# motordriver.net
KiCad netlist of a schematic drawn in EAGLE
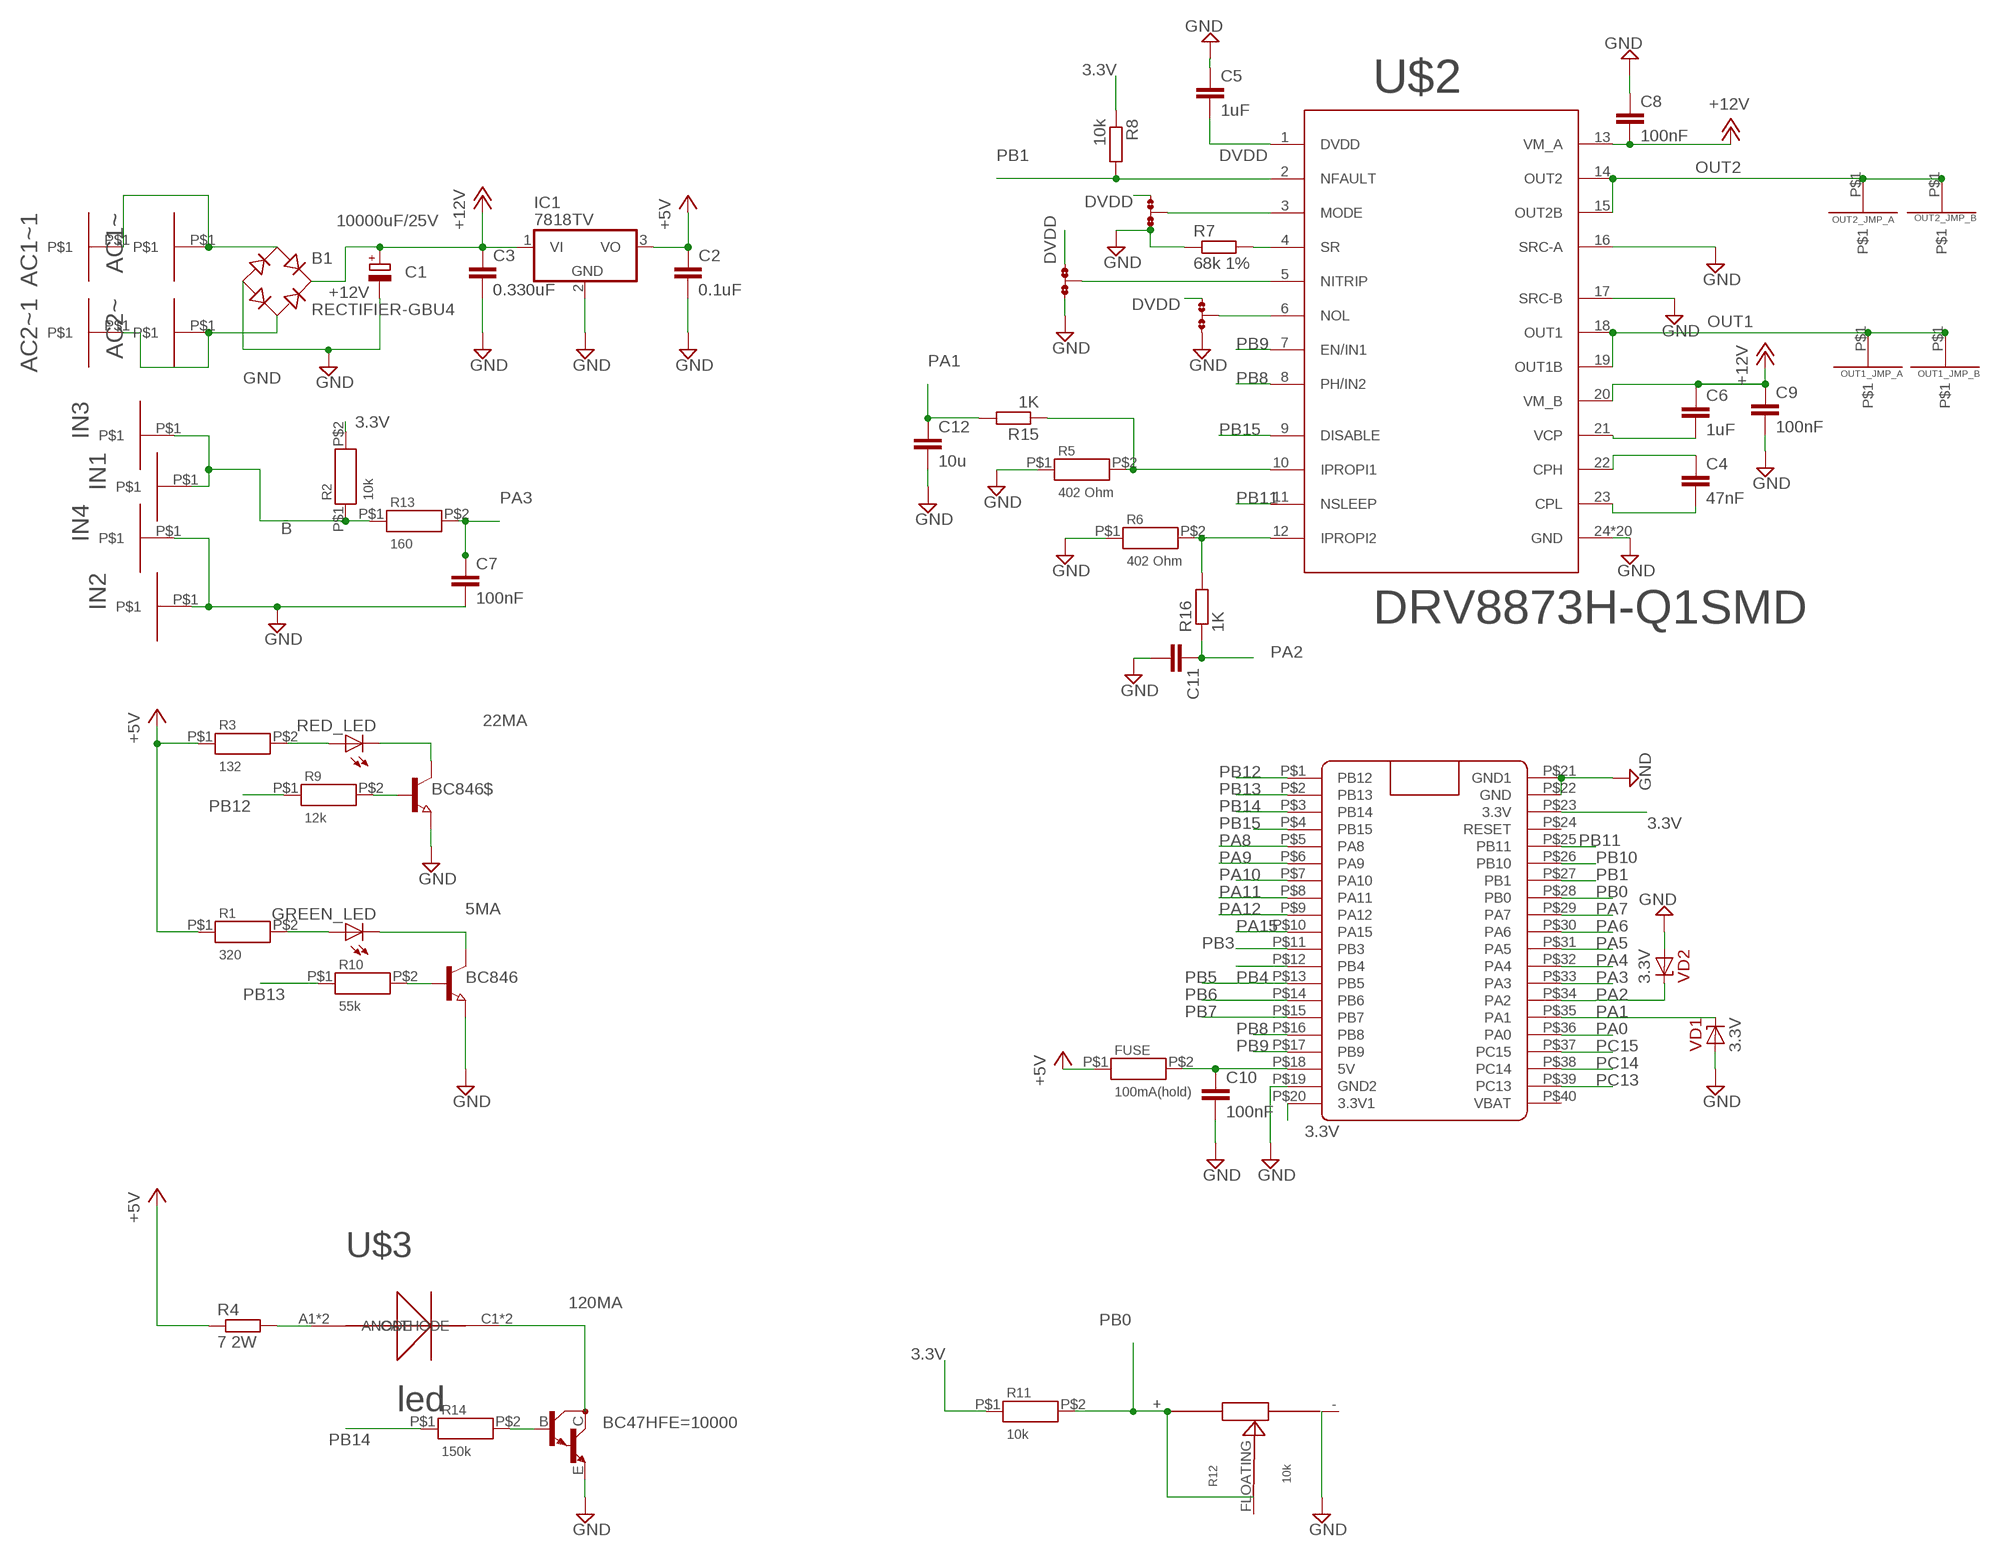
[diagram p0: schematic, sheet 1]

(export (version "E")
  (design (tool "Eeschema 10.0.6"))
  (components
    (comp (ref "AC1~")
      (value "SMDPAD")
      (footprint "eagle-import:1.5X7MMPAD")
      (libsource (lib "eagle-import") (part "SMDPAD"))
    )
    (comp (ref "AC1~1")
      (value "SMDPAD")
      (footprint "eagle-import:1.5X7MMPAD")
      (libsource (lib "eagle-import") (part "SMDPAD"))
    )
    (comp (ref "AC2~")
      (value "SMDPAD")
      (footprint "eagle-import:1.5X7MMPAD")
      (libsource (lib "eagle-import") (part "SMDPAD"))
    )
    (comp (ref "AC2~1")
      (value "SMDPAD")
      (footprint "eagle-import:1.5X7MMPAD")
      (libsource (lib "eagle-import") (part "SMDPAD"))
    )
    (comp (ref "B1")
      (value "RECTIFIER-GBU4")
      (footprint "eagle-import:GBU4")
      (libsource (lib "eagle-import") (part "RECTIFIER-GBU4"))
    )
    (comp (ref "BC47HFE=10000")
      (value "MMBTA14LT1")
      (footprint "eagle-import:SOT23-BEC")
      (libsource (lib "eagle-import") (part "MMBTA14LT1"))
    )
    (comp (ref "BC846")
      (value "NPN-TRANSISTOR_SOT23")
      (footprint "eagle-import:SOT23")
      (libsource (lib "eagle-import") (part "NPN-TRANSISTOR_SOT23"))
    )
    (comp (ref "BC846$")
      (value "NPN-TRANSISTOR_SOT23")
      (footprint "eagle-import:SOT23")
      (libsource (lib "eagle-import") (part "NPN-TRANSISTOR_SOT23"))
    )
    (comp (ref "C1")
      (value "10000uF/25V")
      (footprint "eagle-import:E7,5-18")
      (libsource (lib "eagle-import") (part "CPOL-EUE7.5-18"))
    )
    (comp (ref "C2")
      (value "0.1uF")
      (footprint "eagle-import:C1206")
      (libsource (lib "eagle-import") (part "C-EUC1206"))
    )
    (comp (ref "C3")
      (value "0.330uF")
      (footprint "eagle-import:C1206")
      (libsource (lib "eagle-import") (part "C-EUC1206"))
    )
    (comp (ref "C4")
      (value "47nF")
      (footprint "eagle-import:C1206K")
      (libsource (lib "eagle-import") (part "C-EUC1206K"))
    )
    (comp (ref "C5")
      (value "1uF")
      (footprint "eagle-import:C1206K")
      (libsource (lib "eagle-import") (part "C-EUC1206K"))
    )
    (comp (ref "C6")
      (value "1uF")
      (footprint "eagle-import:C1206K")
      (libsource (lib "eagle-import") (part "C-EUC1206K"))
    )
    (comp (ref "C7")
      (value "100nF")
      (footprint "eagle-import:C1206")
      (libsource (lib "eagle-import") (part "C-EUC1206"))
    )
    (comp (ref "C8")
      (value "100nF")
      (footprint "eagle-import:C0805")
      (libsource (lib "eagle-import") (part "C-EUC0805"))
    )
    (comp (ref "C9")
      (value "100nF")
      (footprint "eagle-import:C0805")
      (libsource (lib "eagle-import") (part "C-EUC0805"))
    )
    (comp (ref "C10")
      (value "100nF")
      (footprint "eagle-import:C0805K")
      (libsource (lib "eagle-import") (part "C-EUC0805K"))
    )
    (comp (ref "C11")
      (value "C-EUC0805K")
      (footprint "eagle-import:C0805K")
      (libsource (lib "eagle-import") (part "C-EUC0805K"))
    )
    (comp (ref "C12")
      (value "10u")
      (footprint "eagle-import:C0805K")
      (libsource (lib "eagle-import") (part "C-EUC0805K"))
    )
    (comp (ref "FUSE")
      (value "100mA(hold)")
      (footprint "eagle-import:0805")
      (libsource (lib "eagle-import") (part "RESISTOR0805_SMD"))
    )
    (comp (ref "GREEN_LED")
      (value "LEDCHIPLED_0805")
      (footprint "eagle-import:CHIPLED_0805")
      (libsource (lib "eagle-import") (part "LEDCHIPLED_0805"))
    )
    (comp (ref "IC1")
      (value "7818TV")
      (footprint "eagle-import:TO220V")
      (libsource (lib "eagle-import") (part "78TV18"))
    )
    (comp (ref "IN1")
      (value "SMDPAD")
      (footprint "eagle-import:1.5X7MMPAD")
      (libsource (lib "eagle-import") (part "SMDPAD"))
    )
    (comp (ref "IN2")
      (value "SMDPAD")
      (footprint "eagle-import:1.5X7MMPAD")
      (libsource (lib "eagle-import") (part "SMDPAD"))
    )
    (comp (ref "IN3")
      (value "SMDPAD")
      (footprint "eagle-import:1.5X7MMPAD")
      (libsource (lib "eagle-import") (part "SMDPAD"))
    )
    (comp (ref "IN4")
      (value "SMDPAD")
      (footprint "eagle-import:1.5X7MMPAD")
      (libsource (lib "eagle-import") (part "SMDPAD"))
    )
    (comp (ref "JMP1")
      (value "0R-JUMPA")
      (footprint "eagle-import:A0R-JMP")
      (libsource (lib "eagle-import") (part "0R-JUMPA"))
    )
    (comp (ref "JMP2")
      (value "0R-JUMPA")
      (footprint "eagle-import:A0R-JMP")
      (libsource (lib "eagle-import") (part "0R-JUMPA"))
    )
    (comp (ref "JMP3")
      (value "0R-JUMPA")
      (footprint "eagle-import:A0R-JMP")
      (libsource (lib "eagle-import") (part "0R-JUMPA"))
    )
    (comp (ref "OUT1_JMP_A")
      (value "SMDPAD")
      (footprint "eagle-import:1.5X7MMPAD")
      (libsource (lib "eagle-import") (part "SMDPAD"))
    )
    (comp (ref "OUT1_JMP_B")
      (value "SMDPAD")
      (footprint "eagle-import:1.5X7MMPAD")
      (libsource (lib "eagle-import") (part "SMDPAD"))
    )
    (comp (ref "OUT2_JMP_A")
      (value "SMDPAD")
      (footprint "eagle-import:1.5X7MMPAD")
      (libsource (lib "eagle-import") (part "SMDPAD"))
    )
    (comp (ref "OUT2_JMP_B")
      (value "SMDPAD")
      (footprint "eagle-import:1.5X7MMPAD")
      (libsource (lib "eagle-import") (part "SMDPAD"))
    )
    (comp (ref "R1")
      (value "320")
      (footprint "eagle-import:0805")
      (libsource (lib "eagle-import") (part "RESISTOR0805_SMD"))
    )
    (comp (ref "R2")
      (value "10k")
      (footprint "eagle-import:0805")
      (libsource (lib "eagle-import") (part "RESISTOR0805_SMD"))
    )
    (comp (ref "R3")
      (value "132")
      (footprint "eagle-import:0805")
      (libsource (lib "eagle-import") (part "RESISTOR0805_SMD"))
    )
    (comp (ref "R4")
      (value "7 2W")
      (footprint "eagle-import:R1210")
      (libsource (lib "eagle-import") (part "R-EU_R1210"))
    )
    (comp (ref "R5")
      (value "402 Ohm")
      (footprint "eagle-import:0805")
      (libsource (lib "eagle-import") (part "RESISTOR0805_SMD"))
    )
    (comp (ref "R6")
      (value "402 Ohm")
      (footprint "eagle-import:0805")
      (libsource (lib "eagle-import") (part "RESISTOR0805_SMD"))
    )
    (comp (ref "R7")
      (value "68k 1%")
      (footprint "eagle-import:R0805")
      (libsource (lib "eagle-import") (part "R-EU_R0805"))
    )
    (comp (ref "R8")
      (value "10k")
      (footprint "eagle-import:R0805")
      (libsource (lib "eagle-import") (part "R-EU_R0805"))
    )
    (comp (ref "R9")
      (value "12k")
      (footprint "eagle-import:0805")
      (libsource (lib "eagle-import") (part "RESISTOR0805_SMD"))
    )
    (comp (ref "R10")
      (value "55k")
      (footprint "eagle-import:0805")
      (libsource (lib "eagle-import") (part "RESISTOR0805_SMD"))
    )
    (comp (ref "R11")
      (value "10k")
      (footprint "eagle-import:0805")
      (libsource (lib "eagle-import") (part "RESISTOR0805_SMD"))
    )
    (comp (ref "R12")
      (value "10k")
      (footprint "eagle-import:3X1MM")
      (libsource (lib "eagle-import") (part "POTENTIOMETER"))
    )
    (comp (ref "R13")
      (value "160")
      (footprint "eagle-import:0805")
      (libsource (lib "eagle-import") (part "RESISTOR0805_SMD"))
    )
    (comp (ref "R14")
      (value "150k")
      (footprint "eagle-import:0805")
      (libsource (lib "eagle-import") (part "RESISTOR0805_SMD"))
    )
    (comp (ref "R15")
      (value "1K")
      (footprint "eagle-import:R0805")
      (libsource (lib "eagle-import") (part "R-EU_R0805"))
    )
    (comp (ref "R16")
      (value "1K")
      (footprint "eagle-import:R0805")
      (libsource (lib "eagle-import") (part "R-EU_R0805"))
    )
    (comp (ref "RED_LED")
      (value "LEDCHIPLED_0805")
      (footprint "eagle-import:CHIPLED_0805")
      (libsource (lib "eagle-import") (part "LEDCHIPLED_0805"))
    )
    (comp (ref "U$1")
      (value "BLUE_PILL")
      (footprint "eagle-import:BLUE_PILL")
      (libsource (lib "eagle-import") (part "BLUE_PILL"))
    )
    (comp (ref "U$2")
      (value "DRV8873H-Q1SMD")
      (footprint "eagle-import:HTSSOP24")
      (libsource (lib "eagle-import") (part "DRV8873H-Q1SMD"))
    )
    (comp (ref "U$3")
      (value "POWER_LED")
      (footprint "eagle-import:OSRAMLED")
      (libsource (lib "eagle-import") (part "POWER_LED"))
    )
    (comp (ref "VD1")
      (value "3.3V")
      (footprint "eagle-import:DO35-7")
      (libsource (lib "eagle-import") (part "?5.6V(1N5232)"))
    )
    (comp (ref "VD2")
      (value "3.3V")
      (footprint "eagle-import:DO35-7")
      (libsource (lib "eagle-import") (part "?5.6V(1N5232)"))
    )
  )
  (nets
    (net (code "1") (name "+5V") (class "Default")
      (node (ref "C2") (pin "1") (pinfunction "1_1") (pintype "passive"))
      (node (ref "FUSE") (pin "P$1") (pinfunction "P$1_P$1") (pintype "bidirectional"))
      (node (ref "IC1") (pin "3") (pinfunction "VO_3") (pintype "passive"))
      (node (ref "R1") (pin "P$1") (pinfunction "P$1_P$1") (pintype "bidirectional"))
      (node (ref "R3") (pin "P$1") (pinfunction "P$1_P$1") (pintype "bidirectional"))
      (node (ref "R4") (pin "1") (pinfunction "1_1") (pintype "passive"))
    )
    (net (code "2") (name "+12V") (class "Default")
      (node (ref "B1") (pin "+") (pinfunction "+_+") (pintype "passive"))
      (node (ref "C1") (pin "+") (pinfunction "+_+") (pintype "passive"))
      (node (ref "C3") (pin "1") (pinfunction "1_1") (pintype "passive"))
      (node (ref "C6") (pin "1") (pinfunction "1_1") (pintype "passive"))
      (node (ref "C8") (pin "2") (pinfunction "2_2") (pintype "passive"))
      (node (ref "C9") (pin "1") (pinfunction "1_1") (pintype "passive"))
      (node (ref "IC1") (pin "1") (pinfunction "VI_1") (pintype "input"))
      (node (ref "U$2") (pin "13") (pinfunction "VM_A_13") (pintype "power_in"))
      (node (ref "U$2") (pin "20") (pinfunction "VM_B_20") (pintype "power_in"))
    )
    (net (code "3") (name "/3.3V") (class "Default")
      (node (ref "R11") (pin "P$1") (pinfunction "P$1_P$1") (pintype "bidirectional"))
      (node (ref "R2") (pin "P$2") (pinfunction "P$2_P$2") (pintype "bidirectional"))
      (node (ref "R8") (pin "1") (pinfunction "1_1") (pintype "passive"))
      (node (ref "U$1") (pin "P$20") (pinfunction "3.3V1_P$20") (pintype "bidirectional"))
      (node (ref "U$1") (pin "P$23") (pinfunction "3.3V_P$23") (pintype "bidirectional"))
    )
    (net (code "4") (name "/5MA") (class "Default")
      (node (ref "BC846") (pin "3") (pinfunction "C_3") (pintype "passive"))
      (node (ref "GREEN_LED") (pin "C") (pinfunction "C_C") (pintype "passive"))
    )
    (net (code "5") (name "/22MA") (class "Default")
      (node (ref "BC846$") (pin "3") (pinfunction "C_3") (pintype "passive"))
      (node (ref "RED_LED") (pin "C") (pinfunction "C_C") (pintype "passive"))
    )
    (net (code "6") (name "/120MA") (class "Default")
      (node (ref "BC47HFE=10000") (pin "C") (pinfunction "C_C") (pintype "passive"))
      (node (ref "U$3") (pin "C1") (pinfunction "CATHODE_C1") (pintype "bidirectional"))
      (node (ref "U$3") (pin "C2") (pinfunction "CATHODE_C2") (pintype "bidirectional"))
    )
    (net (code "7") (name "/B") (class "Default")
      (node (ref "IN1") (pin "P$1") (pinfunction "P$1_P$1") (pintype "bidirectional"))
      (node (ref "IN3") (pin "P$1") (pinfunction "P$1_P$1") (pintype "bidirectional"))
      (node (ref "R13") (pin "P$1") (pinfunction "P$1_P$1") (pintype "bidirectional"))
      (node (ref "R2") (pin "P$1") (pinfunction "P$1_P$1") (pintype "bidirectional"))
    )
    (net (code "8") (name "/DVDD") (class "Default")
      (node (ref "C5") (pin "2") (pinfunction "2_2") (pintype "passive"))
      (node (ref "JMP1") (pin "1") (pinfunction "1_1") (pintype "passive"))
      (node (ref "JMP2") (pin "1") (pinfunction "1_1") (pintype "passive"))
      (node (ref "JMP3") (pin "1") (pinfunction "1_1") (pintype "passive"))
      (node (ref "U$2") (pin "1") (pinfunction "DVDD_1") (pintype "power_in"))
    )
    (net (code "9") (name "/OUT1") (class "Default")
      (node (ref "OUT1_JMP_A") (pin "P$1") (pinfunction "P$1_P$1") (pintype "bidirectional"))
      (node (ref "OUT1_JMP_B") (pin "P$1") (pinfunction "P$1_P$1") (pintype "bidirectional"))
      (node (ref "U$2") (pin "18") (pinfunction "OUT1_18") (pintype "output"))
      (node (ref "U$2") (pin "19") (pinfunction "OUT1B_19") (pintype "output"))
    )
    (net (code "10") (name "/OUT2") (class "Default")
      (node (ref "OUT2_JMP_A") (pin "P$1") (pinfunction "P$1_P$1") (pintype "bidirectional"))
      (node (ref "OUT2_JMP_B") (pin "P$1") (pinfunction "P$1_P$1") (pintype "bidirectional"))
      (node (ref "U$2") (pin "14") (pinfunction "OUT2_14") (pintype "output"))
      (node (ref "U$2") (pin "15") (pinfunction "OUT2B_15") (pintype "output"))
    )
    (net (code "11") (name "/PA0") (class "Default")
      (node (ref "U$1") (pin "P$36") (pinfunction "PA0_P$36") (pintype "bidirectional"))
    )
    (net (code "12") (name "/PA1") (class "Default")
      (node (ref "C12") (pin "1") (pinfunction "1_1") (pintype "passive"))
      (node (ref "R15") (pin "2") (pinfunction "2_2") (pintype "passive"))
      (node (ref "U$1") (pin "P$35") (pinfunction "PA1_P$35") (pintype "bidirectional"))
      (node (ref "VD1") (pin "C") (pinfunction "C_C") (pintype "passive"))
    )
    (net (code "13") (name "/PA2") (class "Default")
      (node (ref "C11") (pin "1") (pinfunction "1_1") (pintype "passive"))
      (node (ref "R16") (pin "1") (pinfunction "1_1") (pintype "passive"))
      (node (ref "U$1") (pin "P$34") (pinfunction "PA2_P$34") (pintype "bidirectional"))
      (node (ref "VD2") (pin "C") (pinfunction "C_C") (pintype "passive"))
    )
    (net (code "14") (name "/PA3") (class "Default")
      (node (ref "C7") (pin "1") (pinfunction "1_1") (pintype "passive"))
      (node (ref "R13") (pin "P$2") (pinfunction "P$2_P$2") (pintype "bidirectional"))
      (node (ref "U$1") (pin "P$33") (pinfunction "PA3_P$33") (pintype "bidirectional"))
    )
    (net (code "15") (name "/PA4") (class "Default")
      (node (ref "U$1") (pin "P$32") (pinfunction "PA4_P$32") (pintype "bidirectional"))
    )
    (net (code "16") (name "/PA5") (class "Default")
      (node (ref "U$1") (pin "P$31") (pinfunction "PA5_P$31") (pintype "bidirectional"))
    )
    (net (code "17") (name "/PA6") (class "Default")
      (node (ref "U$1") (pin "P$30") (pinfunction "PA6_P$30") (pintype "bidirectional"))
    )
    (net (code "18") (name "/PA7") (class "Default")
      (node (ref "U$1") (pin "P$29") (pinfunction "PA7_P$29") (pintype "bidirectional"))
    )
    (net (code "19") (name "/PA8") (class "Default")
      (node (ref "U$1") (pin "P$5") (pinfunction "PA8_P$5") (pintype "bidirectional"))
    )
    (net (code "20") (name "/PA9") (class "Default")
      (node (ref "U$1") (pin "P$6") (pinfunction "PA9_P$6") (pintype "bidirectional"))
    )
    (net (code "21") (name "/PA10") (class "Default")
      (node (ref "U$1") (pin "P$7") (pinfunction "PA10_P$7") (pintype "bidirectional"))
    )
    (net (code "22") (name "/PA11") (class "Default")
      (node (ref "U$1") (pin "P$8") (pinfunction "PA11_P$8") (pintype "bidirectional"))
    )
    (net (code "23") (name "/PA12") (class "Default")
      (node (ref "U$1") (pin "P$9") (pinfunction "PA12_P$9") (pintype "bidirectional"))
    )
    (net (code "24") (name "/PA15") (class "Default")
      (node (ref "U$1") (pin "P$10") (pinfunction "PA15_P$10") (pintype "bidirectional"))
    )
    (net (code "25") (name "/PB0") (class "Default")
      (node (ref "R11") (pin "P$2") (pinfunction "P$2_P$2") (pintype "bidirectional"))
      (node (ref "R12") (pin "+") (pinfunction "+_+") (pintype "bidirectional"))
      (node (ref "R12") (pin "FLOATING") (pinfunction "FLOATING_FLOATING") (pintype "bidirectional"))
      (node (ref "U$1") (pin "P$28") (pinfunction "PB0_P$28") (pintype "bidirectional"))
    )
    (net (code "26") (name "/PB1") (class "Default")
      (node (ref "R8") (pin "2") (pinfunction "2_2") (pintype "passive"))
      (node (ref "U$1") (pin "P$27") (pinfunction "PB1_P$27") (pintype "bidirectional"))
      (node (ref "U$2") (pin "2") (pinfunction "NFAULT_2") (pintype "bidirectional"))
    )
    (net (code "27") (name "/PB3") (class "Default")
      (node (ref "U$1") (pin "P$11") (pinfunction "PB3_P$11") (pintype "bidirectional"))
    )
    (net (code "28") (name "/PB4") (class "Default")
      (node (ref "U$1") (pin "P$12") (pinfunction "PB4_P$12") (pintype "bidirectional"))
    )
    (net (code "29") (name "/PB5") (class "Default")
      (node (ref "U$1") (pin "P$13") (pinfunction "PB5_P$13") (pintype "bidirectional"))
    )
    (net (code "30") (name "/PB6") (class "Default")
      (node (ref "U$1") (pin "P$14") (pinfunction "PB6_P$14") (pintype "bidirectional"))
    )
    (net (code "31") (name "/PB7") (class "Default")
      (node (ref "U$1") (pin "P$15") (pinfunction "PB7_P$15") (pintype "bidirectional"))
    )
    (net (code "32") (name "/PB8") (class "Default")
      (node (ref "U$1") (pin "P$16") (pinfunction "PB8_P$16") (pintype "bidirectional"))
      (node (ref "U$2") (pin "8") (pinfunction "PH/IN2_8") (pintype "input"))
    )
    (net (code "33") (name "/PB9") (class "Default")
      (node (ref "U$1") (pin "P$17") (pinfunction "PB9_P$17") (pintype "bidirectional"))
      (node (ref "U$2") (pin "7") (pinfunction "EN/IN1_7") (pintype "input"))
    )
    (net (code "34") (name "/PB10") (class "Default")
      (node (ref "U$1") (pin "P$26") (pinfunction "PB10_P$26") (pintype "bidirectional"))
    )
    (net (code "35") (name "/PB11") (class "Default")
      (node (ref "U$1") (pin "P$25") (pinfunction "PB11_P$25") (pintype "bidirectional"))
      (node (ref "U$2") (pin "11") (pinfunction "NSLEEP_11") (pintype "input"))
    )
    (net (code "36") (name "/PB12") (class "Default")
      (node (ref "R9") (pin "P$1") (pinfunction "P$1_P$1") (pintype "bidirectional"))
      (node (ref "U$1") (pin "P$1") (pinfunction "PB12_P$1") (pintype "bidirectional"))
    )
    (net (code "37") (name "/PB13") (class "Default")
      (node (ref "R10") (pin "P$1") (pinfunction "P$1_P$1") (pintype "bidirectional"))
      (node (ref "U$1") (pin "P$2") (pinfunction "PB13_P$2") (pintype "bidirectional"))
    )
    (net (code "38") (name "/PB14") (class "Default")
      (node (ref "R14") (pin "P$1") (pinfunction "P$1_P$1") (pintype "bidirectional"))
      (node (ref "U$1") (pin "P$3") (pinfunction "PB14_P$3") (pintype "bidirectional"))
    )
    (net (code "39") (name "/PB15") (class "Default")
      (node (ref "U$1") (pin "P$4") (pinfunction "PB15_P$4") (pintype "bidirectional"))
      (node (ref "U$2") (pin "9") (pinfunction "DISABLE_9") (pintype "input"))
    )
    (net (code "40") (name "/PC13") (class "Default")
      (node (ref "U$1") (pin "P$39") (pinfunction "PC13_P$39") (pintype "bidirectional"))
    )
    (net (code "41") (name "/PC14") (class "Default")
      (node (ref "U$1") (pin "P$38") (pinfunction "PC14_P$38") (pintype "bidirectional"))
    )
    (net (code "42") (name "/PC15") (class "Default")
      (node (ref "U$1") (pin "P$37") (pinfunction "PC15_P$37") (pintype "bidirectional"))
    )
    (net (code "43") (name "GND") (class "Default")
      (node (ref "B1") (pin "-") (pinfunction "-_-") (pintype "passive"))
      (node (ref "BC47HFE=10000") (pin "E") (pinfunction "E_E") (pintype "passive"))
      (node (ref "BC846") (pin "2") (pinfunction "E_2") (pintype "passive"))
      (node (ref "BC846$") (pin "2") (pinfunction "E_2") (pintype "passive"))
      (node (ref "C1") (pin "-") (pinfunction "-_-") (pintype "passive"))
      (node (ref "C10") (pin "2") (pinfunction "2_2") (pintype "passive"))
      (node (ref "C11") (pin "2") (pinfunction "2_2") (pintype "passive"))
      (node (ref "C12") (pin "2") (pinfunction "2_2") (pintype "passive"))
      (node (ref "C2") (pin "2") (pinfunction "2_2") (pintype "passive"))
      (node (ref "C3") (pin "2") (pinfunction "2_2") (pintype "passive"))
      (node (ref "C5") (pin "1") (pinfunction "1_1") (pintype "passive"))
      (node (ref "C7") (pin "2") (pinfunction "2_2") (pintype "passive"))
      (node (ref "C8") (pin "1") (pinfunction "1_1") (pintype "passive"))
      (node (ref "C9") (pin "2") (pinfunction "2_2") (pintype "passive"))
      (node (ref "IC1") (pin "2") (pinfunction "GND_2") (pintype "passive"))
      (node (ref "IN2") (pin "P$1") (pinfunction "P$1_P$1") (pintype "bidirectional"))
      (node (ref "IN4") (pin "P$1") (pinfunction "P$1_P$1") (pintype "bidirectional"))
      (node (ref "JMP1") (pin "3") (pinfunction "3_3") (pintype "passive"))
      (node (ref "JMP2") (pin "3") (pinfunction "3_3") (pintype "passive"))
      (node (ref "JMP3") (pin "3") (pinfunction "3_3") (pintype "passive"))
      (node (ref "R12") (pin "-") (pinfunction "-_-") (pintype "bidirectional"))
      (node (ref "R5") (pin "P$1") (pinfunction "P$1_P$1") (pintype "bidirectional"))
      (node (ref "R6") (pin "P$1") (pinfunction "P$1_P$1") (pintype "bidirectional"))
      (node (ref "R7") (pin "1") (pinfunction "1_1") (pintype "passive"))
      (node (ref "U$1") (pin "P$19") (pinfunction "GND2_P$19") (pintype "bidirectional"))
      (node (ref "U$1") (pin "P$21") (pinfunction "GND1_P$21") (pintype "power_in"))
      (node (ref "U$1") (pin "P$22") (pinfunction "GND_P$22") (pintype "bidirectional"))
      (node (ref "U$2") (pin "16") (pinfunction "SRC-A_16") (pintype "output"))
      (node (ref "U$2") (pin "17") (pinfunction "SRC-B_17") (pintype "output"))
      (node (ref "U$2") (pin "24") (pinfunction "GND_24") (pintype "power_in"))
      (node (ref "U$2") (pin "GND_") (pinfunction "GND_GND_") (pintype "power_in"))
      (node (ref "U$2") (pin "P$1") (pinfunction "GND_P$1") (pintype "power_in"))
      (node (ref "U$2") (pin "P$10") (pinfunction "GND_P$10") (pintype "power_in"))
      (node (ref "U$2") (pin "P$11") (pinfunction "GND_P$11") (pintype "power_in"))
      (node (ref "U$2") (pin "P$12") (pinfunction "GND_P$12") (pintype "power_in"))
      (node (ref "U$2") (pin "P$13") (pinfunction "GND_P$13") (pintype "power_in"))
      (node (ref "U$2") (pin "P$14") (pinfunction "GND_P$14") (pintype "power_in"))
      (node (ref "U$2") (pin "P$15") (pinfunction "GND_P$15") (pintype "power_in"))
      (node (ref "U$2") (pin "P$16") (pinfunction "GND_P$16") (pintype "power_in"))
      (node (ref "U$2") (pin "P$18") (pinfunction "GND_P$18") (pintype "power_in"))
      (node (ref "U$2") (pin "P$19") (pinfunction "GND_P$19") (pintype "power_in"))
      (node (ref "U$2") (pin "P$2") (pinfunction "GND_P$2") (pintype "power_in"))
      (node (ref "U$2") (pin "P$3") (pinfunction "GND_P$3") (pintype "power_in"))
      (node (ref "U$2") (pin "P$4") (pinfunction "GND_P$4") (pintype "power_in"))
      (node (ref "U$2") (pin "P$5") (pinfunction "GND_P$5") (pintype "power_in"))
      (node (ref "U$2") (pin "P$6") (pinfunction "GND_P$6") (pintype "power_in"))
      (node (ref "U$2") (pin "P$7") (pinfunction "GND_P$7") (pintype "power_in"))
      (node (ref "U$2") (pin "P$8") (pinfunction "GND_P$8") (pintype "power_in"))
      (node (ref "U$2") (pin "P$9") (pinfunction "GND_P$9") (pintype "power_in"))
      (node (ref "VD1") (pin "A") (pinfunction "A_A") (pintype "passive"))
      (node (ref "VD2") (pin "A") (pinfunction "A_A") (pintype "passive"))
    )
    (net (code "44") (name "Net-(AC1~-PadP$1)") (class "Default")
      (node (ref "AC1~") (pin "P$1") (pinfunction "P$1_P$1") (pintype "bidirectional"))
      (node (ref "AC1~1") (pin "P$1") (pinfunction "P$1_P$1") (pintype "bidirectional"))
      (node (ref "B1") (pin "AC1") (pinfunction "AC1_AC1") (pintype "passive"))
    )
    (net (code "45") (name "Net-(AC2~-PadP$1)") (class "Default")
      (node (ref "AC2~") (pin "P$1") (pinfunction "P$1_P$1") (pintype "bidirectional"))
      (node (ref "AC2~1") (pin "P$1") (pinfunction "P$1_P$1") (pintype "bidirectional"))
      (node (ref "B1") (pin "AC2") (pinfunction "AC2_AC2") (pintype "passive"))
    )
    (net (code "46") (name "Net-(BC47HFE=10000-PadB)") (class "Default")
      (node (ref "BC47HFE=10000") (pin "B") (pinfunction "B_B") (pintype "passive"))
      (node (ref "R14") (pin "P$2") (pinfunction "P$2_P$2") (pintype "bidirectional"))
    )
    (net (code "47") (name "Net-(BC846$-B)") (class "Default")
      (node (ref "BC846$") (pin "1") (pinfunction "B_1") (pintype "passive"))
      (node (ref "R9") (pin "P$2") (pinfunction "P$2_P$2") (pintype "bidirectional"))
    )
    (net (code "48") (name "Net-(BC846-B)") (class "Default")
      (node (ref "BC846") (pin "1") (pinfunction "B_1") (pintype "passive"))
      (node (ref "R10") (pin "P$2") (pinfunction "P$2_P$2") (pintype "bidirectional"))
    )
    (net (code "49") (name "Net-(GREEN_LED-PadA)") (class "Default")
      (node (ref "GREEN_LED") (pin "A") (pinfunction "A_A") (pintype "passive"))
      (node (ref "R1") (pin "P$2") (pinfunction "P$2_P$2") (pintype "bidirectional"))
    )
    (net (code "50") (name "Net-(R3-PadP$2)") (class "Default")
      (node (ref "R3") (pin "P$2") (pinfunction "P$2_P$2") (pintype "bidirectional"))
      (node (ref "RED_LED") (pin "A") (pinfunction "A_A") (pintype "passive"))
    )
    (net (code "51") (name "Net-(R4-Pad2)") (class "Default")
      (node (ref "R4") (pin "2") (pinfunction "2_2") (pintype "passive"))
      (node (ref "U$3") (pin "A1") (pinfunction "ANODE_A1") (pintype "bidirectional"))
      (node (ref "U$3") (pin "A2") (pinfunction "ANODE_A2") (pintype "bidirectional"))
    )
    (net (code "52") (name "Net-(U$1-5V)") (class "Default")
      (node (ref "C10") (pin "1") (pinfunction "1_1") (pintype "passive"))
      (node (ref "FUSE") (pin "P$2") (pinfunction "P$2_P$2") (pintype "bidirectional"))
      (node (ref "U$1") (pin "P$18") (pinfunction "5V_P$18") (pintype "bidirectional"))
    )
    (net (code "53") (name "Net-(U$2-CPH)") (class "Default")
      (node (ref "C4") (pin "1") (pinfunction "1_1") (pintype "passive"))
      (node (ref "U$2") (pin "22") (pinfunction "CPH_22") (pintype "power_in"))
    )
    (net (code "54") (name "Net-(U$2-CPL)") (class "Default")
      (node (ref "C4") (pin "2") (pinfunction "2_2") (pintype "passive"))
      (node (ref "U$2") (pin "23") (pinfunction "CPL_23") (pintype "power_in"))
    )
    (net (code "55") (name "Net-(U$2-IPROPI1)") (class "Default")
      (node (ref "R15") (pin "1") (pinfunction "1_1") (pintype "passive"))
      (node (ref "R5") (pin "P$2") (pinfunction "P$2_P$2") (pintype "bidirectional"))
      (node (ref "U$2") (pin "10") (pinfunction "IPROPI1_10") (pintype "output"))
    )
    (net (code "56") (name "Net-(U$2-IPROPI2)") (class "Default")
      (node (ref "R16") (pin "2") (pinfunction "2_2") (pintype "passive"))
      (node (ref "R6") (pin "P$2") (pinfunction "P$2_P$2") (pintype "bidirectional"))
      (node (ref "U$2") (pin "12") (pinfunction "IPROPI2_12") (pintype "output"))
    )
    (net (code "57") (name "Net-(U$2-MODE)") (class "Default")
      (node (ref "JMP3") (pin "2") (pinfunction "2_2") (pintype "passive"))
      (node (ref "U$2") (pin "3") (pinfunction "MODE_3") (pintype "input"))
    )
    (net (code "58") (name "Net-(U$2-NITRIP)") (class "Default")
      (node (ref "JMP1") (pin "2") (pinfunction "2_2") (pintype "passive"))
      (node (ref "U$2") (pin "5") (pinfunction "NITRIP_5") (pintype "input"))
    )
    (net (code "59") (name "Net-(U$2-NOL)") (class "Default")
      (node (ref "JMP2") (pin "2") (pinfunction "2_2") (pintype "passive"))
      (node (ref "U$2") (pin "6") (pinfunction "NOL_6") (pintype "input"))
    )
    (net (code "60") (name "Net-(U$2-SR)") (class "Default")
      (node (ref "R7") (pin "2") (pinfunction "2_2") (pintype "passive"))
      (node (ref "U$2") (pin "4") (pinfunction "SR_4") (pintype "input"))
    )
    (net (code "61") (name "Net-(U$2-VCP)") (class "Default")
      (node (ref "C6") (pin "2") (pinfunction "2_2") (pintype "passive"))
      (node (ref "U$2") (pin "21") (pinfunction "VCP_21") (pintype "power_in"))
    )
    (net (code "62") (name "unconnected-(U$1-RESET-PadP$24)") (class "Default")
      (node (ref "U$1") (pin "P$24") (pinfunction "RESET_P$24") (pintype "bidirectional"))
    )
    (net (code "63") (name "unconnected-(U$1-VBAT-PadP$40)") (class "Default")
      (node (ref "U$1") (pin "P$40") (pinfunction "VBAT_P$40") (pintype "bidirectional"))
    )
  )
)
